# W024X.net
KiCad netlist of a schematic drawn in EAGLE
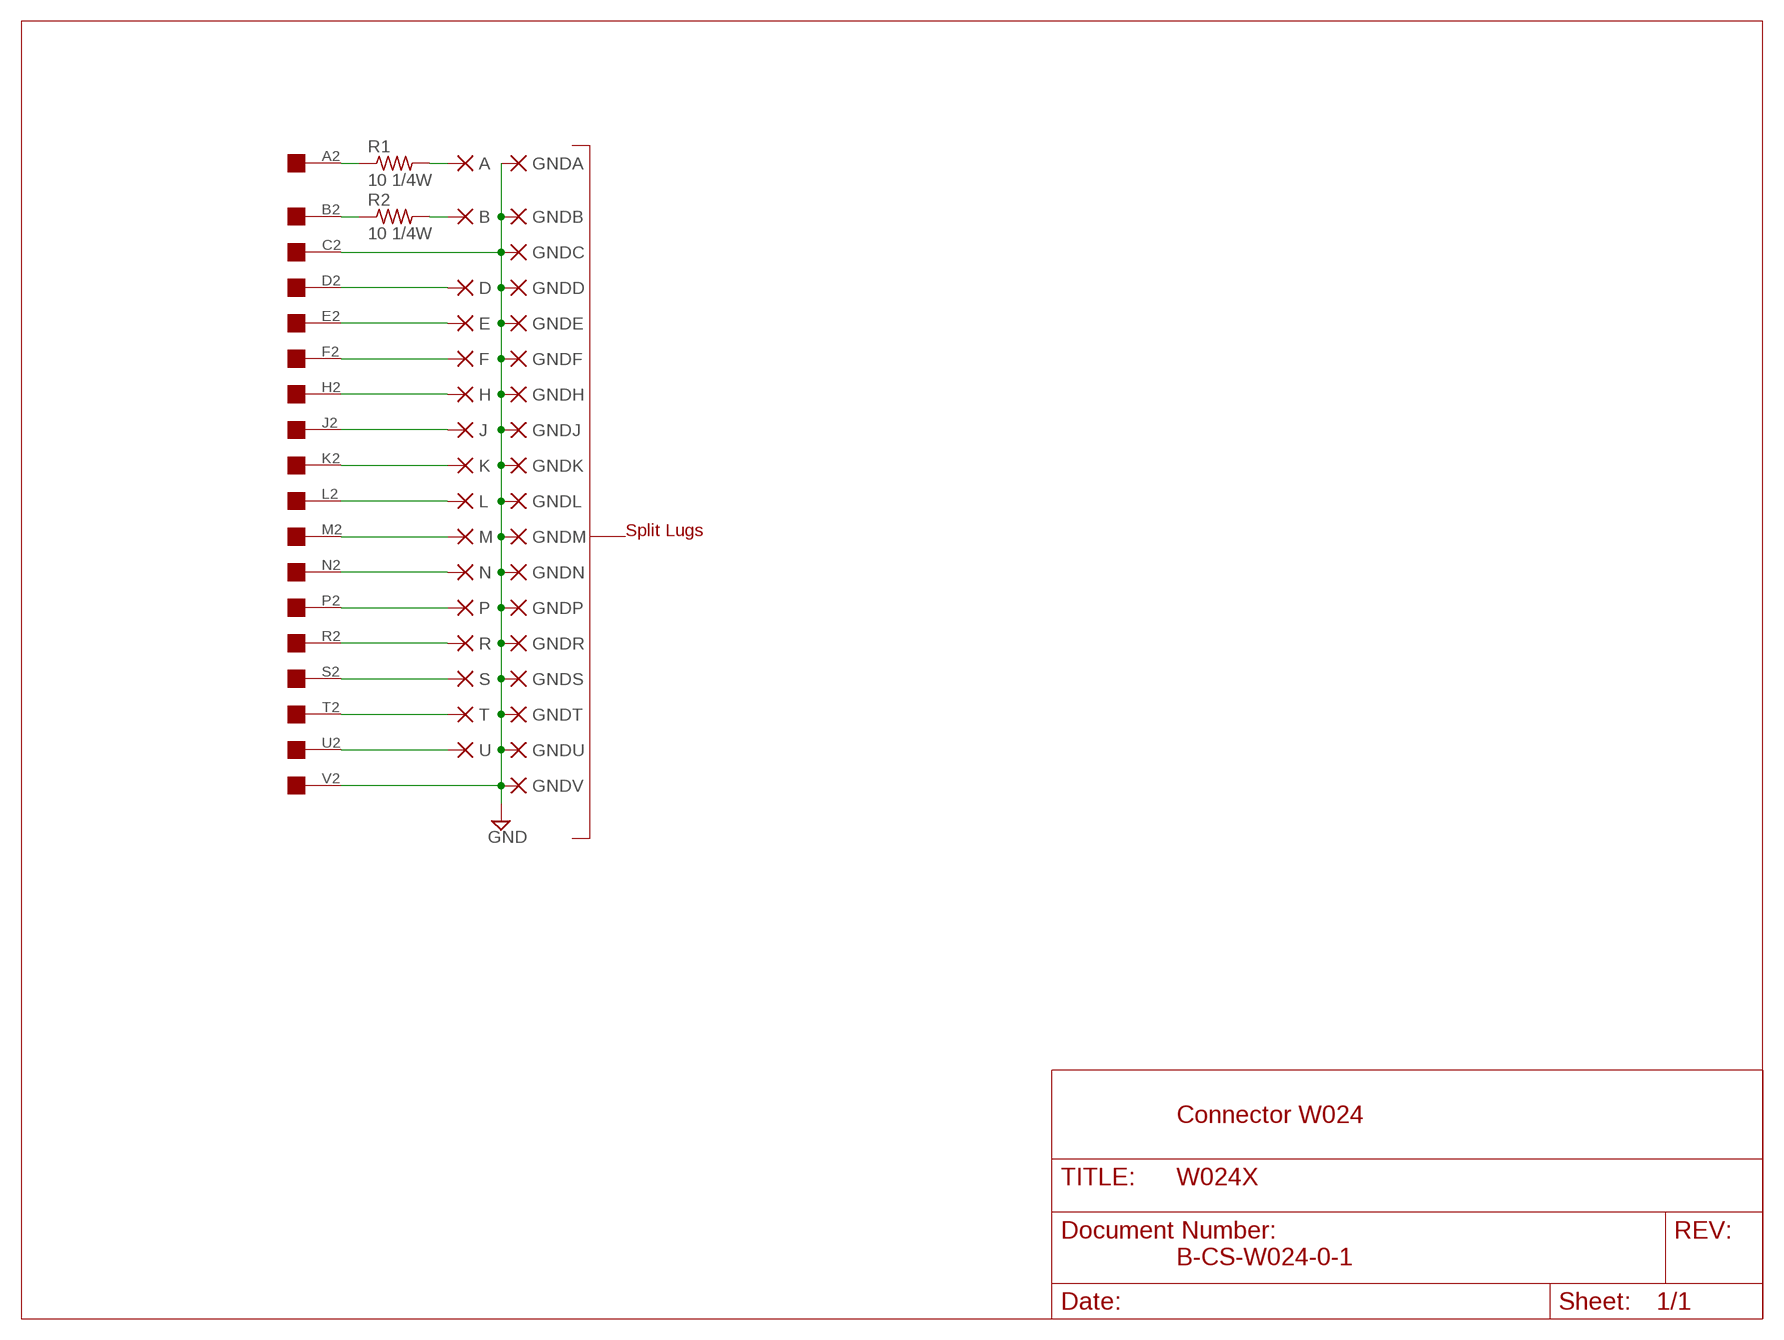
[diagram p0: schematic, sheet 1]

(export (version "E")
  (design (tool "Eeschema 10.0.6"))
  (components
    (comp (ref "A")
      (value "PAD-0465")
      (footprint "eagle-import:0465")
      (libsource (lib "eagle-import") (part "PAD-0465"))
    )
    (comp (ref "B")
      (value "PAD-0465")
      (footprint "eagle-import:0465")
      (libsource (lib "eagle-import") (part "PAD-0465"))
    )
    (comp (ref "D")
      (value "PAD-0465")
      (footprint "eagle-import:0465")
      (libsource (lib "eagle-import") (part "PAD-0465"))
    )
    (comp (ref "E")
      (value "PAD-0465")
      (footprint "eagle-import:0465")
      (libsource (lib "eagle-import") (part "PAD-0465"))
    )
    (comp (ref "F")
      (value "PAD-0465")
      (footprint "eagle-import:0465")
      (libsource (lib "eagle-import") (part "PAD-0465"))
    )
    (comp (ref "GNDA")
      (value "PAD-0465")
      (footprint "eagle-import:0465")
      (libsource (lib "eagle-import") (part "PAD-0465"))
    )
    (comp (ref "GNDB")
      (value "PAD-0465")
      (footprint "eagle-import:0465")
      (libsource (lib "eagle-import") (part "PAD-0465"))
    )
    (comp (ref "GNDC")
      (value "PAD-0465")
      (footprint "eagle-import:0465")
      (libsource (lib "eagle-import") (part "PAD-0465"))
    )
    (comp (ref "GNDD")
      (value "PAD-0465")
      (footprint "eagle-import:0465")
      (libsource (lib "eagle-import") (part "PAD-0465"))
    )
    (comp (ref "GNDE")
      (value "PAD-0465")
      (footprint "eagle-import:0465")
      (libsource (lib "eagle-import") (part "PAD-0465"))
    )
    (comp (ref "GNDF")
      (value "PAD-0465")
      (footprint "eagle-import:0465")
      (libsource (lib "eagle-import") (part "PAD-0465"))
    )
    (comp (ref "GNDH")
      (value "PAD-0465")
      (footprint "eagle-import:0465")
      (libsource (lib "eagle-import") (part "PAD-0465"))
    )
    (comp (ref "GNDJ")
      (value "PAD-0465")
      (footprint "eagle-import:0465")
      (libsource (lib "eagle-import") (part "PAD-0465"))
    )
    (comp (ref "GNDK")
      (value "PAD-0465")
      (footprint "eagle-import:0465")
      (libsource (lib "eagle-import") (part "PAD-0465"))
    )
    (comp (ref "GNDL")
      (value "PAD-0465")
      (footprint "eagle-import:0465")
      (libsource (lib "eagle-import") (part "PAD-0465"))
    )
    (comp (ref "GNDM")
      (value "PAD-0465")
      (footprint "eagle-import:0465")
      (libsource (lib "eagle-import") (part "PAD-0465"))
    )
    (comp (ref "GNDN")
      (value "PAD-0465")
      (footprint "eagle-import:0465")
      (libsource (lib "eagle-import") (part "PAD-0465"))
    )
    (comp (ref "GNDP")
      (value "PAD-0465")
      (footprint "eagle-import:0465")
      (libsource (lib "eagle-import") (part "PAD-0465"))
    )
    (comp (ref "GNDR")
      (value "PAD-0465")
      (footprint "eagle-import:0465")
      (libsource (lib "eagle-import") (part "PAD-0465"))
    )
    (comp (ref "GNDS")
      (value "PAD-0465")
      (footprint "eagle-import:0465")
      (libsource (lib "eagle-import") (part "PAD-0465"))
    )
    (comp (ref "GNDT")
      (value "PAD-0465")
      (footprint "eagle-import:0465")
      (libsource (lib "eagle-import") (part "PAD-0465"))
    )
    (comp (ref "GNDU")
      (value "PAD-0465")
      (footprint "eagle-import:0465")
      (libsource (lib "eagle-import") (part "PAD-0465"))
    )
    (comp (ref "GNDV")
      (value "PAD-0465")
      (footprint "eagle-import:0465")
      (libsource (lib "eagle-import") (part "PAD-0465"))
    )
    (comp (ref "H")
      (value "PAD-0465")
      (footprint "eagle-import:0465")
      (libsource (lib "eagle-import") (part "PAD-0465"))
    )
    (comp (ref "J")
      (value "PAD-0465")
      (footprint "eagle-import:0465")
      (libsource (lib "eagle-import") (part "PAD-0465"))
    )
    (comp (ref "K")
      (value "PAD-0465")
      (footprint "eagle-import:0465")
      (libsource (lib "eagle-import") (part "PAD-0465"))
    )
    (comp (ref "L")
      (value "PAD-0465")
      (footprint "eagle-import:0465")
      (libsource (lib "eagle-import") (part "PAD-0465"))
    )
    (comp (ref "M")
      (value "PAD-0465")
      (footprint "eagle-import:0465")
      (libsource (lib "eagle-import") (part "PAD-0465"))
    )
    (comp (ref "N")
      (value "PAD-0465")
      (footprint "eagle-import:0465")
      (libsource (lib "eagle-import") (part "PAD-0465"))
    )
    (comp (ref "P")
      (value "PAD-0465")
      (footprint "eagle-import:0465")
      (libsource (lib "eagle-import") (part "PAD-0465"))
    )
    (comp (ref "R")
      (value "PAD-0465")
      (footprint "eagle-import:0465")
      (libsource (lib "eagle-import") (part "PAD-0465"))
    )
    (comp (ref "R1")
      (value "10 1/4W")
      (footprint "eagle-import:0207_10")
      (libsource (lib "eagle-import") (part "R-US_0207/10"))
    )
    (comp (ref "R2")
      (value "10 1/4W")
      (footprint "eagle-import:0207_10")
      (libsource (lib "eagle-import") (part "R-US_0207/10"))
    )
    (comp (ref "S")
      (value "PAD-0465")
      (footprint "eagle-import:0465")
      (libsource (lib "eagle-import") (part "PAD-0465"))
    )
    (comp (ref "T")
      (value "PAD-0465")
      (footprint "eagle-import:0465")
      (libsource (lib "eagle-import") (part "PAD-0465"))
    )
    (comp (ref "U")
      (value "PAD-0465")
      (footprint "eagle-import:0465")
      (libsource (lib "eagle-import") (part "PAD-0465"))
    )
    (comp (ref "U$2")
      (value "EDGE-1")
      (footprint "eagle-import:EDGE-CON1")
      (libsource (lib "eagle-import") (part "EDGE-1"))
    )
  )
  (nets
    (net (code "1") (name "GND") (class "Default")
      (node (ref "GNDA") (pin "P$1") (pinfunction "P_P$1") (pintype "passive"))
      (node (ref "GNDB") (pin "P$1") (pinfunction "P_P$1") (pintype "passive"))
      (node (ref "GNDC") (pin "P$1") (pinfunction "P_P$1") (pintype "passive"))
      (node (ref "GNDD") (pin "P$1") (pinfunction "P_P$1") (pintype "passive"))
      (node (ref "GNDE") (pin "P$1") (pinfunction "P_P$1") (pintype "passive"))
      (node (ref "GNDF") (pin "P$1") (pinfunction "P_P$1") (pintype "passive"))
      (node (ref "GNDH") (pin "P$1") (pinfunction "P_P$1") (pintype "passive"))
      (node (ref "GNDJ") (pin "P$1") (pinfunction "P_P$1") (pintype "passive"))
      (node (ref "GNDK") (pin "P$1") (pinfunction "P_P$1") (pintype "passive"))
      (node (ref "GNDL") (pin "P$1") (pinfunction "P_P$1") (pintype "passive"))
      (node (ref "GNDM") (pin "P$1") (pinfunction "P_P$1") (pintype "passive"))
      (node (ref "GNDN") (pin "P$1") (pinfunction "P_P$1") (pintype "passive"))
      (node (ref "GNDP") (pin "P$1") (pinfunction "P_P$1") (pintype "passive"))
      (node (ref "GNDR") (pin "P$1") (pinfunction "P_P$1") (pintype "passive"))
      (node (ref "GNDS") (pin "P$1") (pinfunction "P_P$1") (pintype "passive"))
      (node (ref "GNDT") (pin "P$1") (pinfunction "P_P$1") (pintype "passive"))
      (node (ref "GNDU") (pin "P$1") (pinfunction "P_P$1") (pintype "passive"))
      (node (ref "GNDV") (pin "P$1") (pinfunction "P_P$1") (pintype "passive"))
      (node (ref "U$2") (pin "C2") (pinfunction "1_C2") (pintype "bidirectional"))
      (node (ref "U$2") (pin "V2") (pinfunction "1_V2") (pintype "bidirectional"))
    )
    (net (code "2") (name "Net-(A-P)") (class "Default")
      (node (ref "A") (pin "P$1") (pinfunction "P_P$1") (pintype "passive"))
      (node (ref "R1") (pin "2") (pinfunction "2_2") (pintype "passive"))
    )
    (net (code "3") (name "Net-(B-P)") (class "Default")
      (node (ref "B") (pin "P$1") (pinfunction "P_P$1") (pintype "passive"))
      (node (ref "R2") (pin "2") (pinfunction "2_2") (pintype "passive"))
    )
    (net (code "4") (name "Net-(D-P)") (class "Default")
      (node (ref "D") (pin "P$1") (pinfunction "P_P$1") (pintype "passive"))
      (node (ref "U$2") (pin "D2") (pinfunction "1_D2") (pintype "bidirectional"))
    )
    (net (code "5") (name "Net-(E-P)") (class "Default")
      (node (ref "E") (pin "P$1") (pinfunction "P_P$1") (pintype "passive"))
      (node (ref "U$2") (pin "E2") (pinfunction "1_E2") (pintype "bidirectional"))
    )
    (net (code "6") (name "Net-(F-P)") (class "Default")
      (node (ref "F") (pin "P$1") (pinfunction "P_P$1") (pintype "passive"))
      (node (ref "U$2") (pin "F2") (pinfunction "1_F2") (pintype "bidirectional"))
    )
    (net (code "7") (name "Net-(H-P)") (class "Default")
      (node (ref "H") (pin "P$1") (pinfunction "P_P$1") (pintype "passive"))
      (node (ref "U$2") (pin "H2") (pinfunction "1_H2") (pintype "bidirectional"))
    )
    (net (code "8") (name "Net-(J-P)") (class "Default")
      (node (ref "J") (pin "P$1") (pinfunction "P_P$1") (pintype "passive"))
      (node (ref "U$2") (pin "J2") (pinfunction "1_J2") (pintype "bidirectional"))
    )
    (net (code "9") (name "Net-(K-P)") (class "Default")
      (node (ref "K") (pin "P$1") (pinfunction "P_P$1") (pintype "passive"))
      (node (ref "U$2") (pin "K2") (pinfunction "1_K2") (pintype "bidirectional"))
    )
    (net (code "10") (name "Net-(L-P)") (class "Default")
      (node (ref "L") (pin "P$1") (pinfunction "P_P$1") (pintype "passive"))
      (node (ref "U$2") (pin "L2") (pinfunction "1_L2") (pintype "bidirectional"))
    )
    (net (code "11") (name "Net-(M-P)") (class "Default")
      (node (ref "M") (pin "P$1") (pinfunction "P_P$1") (pintype "passive"))
      (node (ref "U$2") (pin "M2") (pinfunction "1_M2") (pintype "bidirectional"))
    )
    (net (code "12") (name "Net-(N-P)") (class "Default")
      (node (ref "N") (pin "P$1") (pinfunction "P_P$1") (pintype "passive"))
      (node (ref "U$2") (pin "N2") (pinfunction "1_N2") (pintype "bidirectional"))
    )
    (net (code "13") (name "Net-(P-P)") (class "Default")
      (node (ref "P") (pin "P$1") (pinfunction "P_P$1") (pintype "passive"))
      (node (ref "U$2") (pin "P2") (pinfunction "1_P2") (pintype "bidirectional"))
    )
    (net (code "14") (name "Net-(R-P)") (class "Default")
      (node (ref "R") (pin "P$1") (pinfunction "P_P$1") (pintype "passive"))
      (node (ref "U$2") (pin "R2") (pinfunction "1_R2") (pintype "bidirectional"))
    )
    (net (code "15") (name "Net-(S-P)") (class "Default")
      (node (ref "S") (pin "P$1") (pinfunction "P_P$1") (pintype "passive"))
      (node (ref "U$2") (pin "S2") (pinfunction "1_S2") (pintype "bidirectional"))
    )
    (net (code "16") (name "Net-(T-P)") (class "Default")
      (node (ref "T") (pin "P$1") (pinfunction "P_P$1") (pintype "passive"))
      (node (ref "U$2") (pin "T2") (pinfunction "1_T2") (pintype "bidirectional"))
    )
    (net (code "17") (name "Net-(U$2A-1)") (class "Default")
      (node (ref "R1") (pin "1") (pinfunction "1_1") (pintype "passive"))
      (node (ref "U$2") (pin "A2") (pinfunction "1_A2") (pintype "bidirectional"))
    )
    (net (code "18") (name "Net-(U$2B-1)") (class "Default")
      (node (ref "R2") (pin "1") (pinfunction "1_1") (pintype "passive"))
      (node (ref "U$2") (pin "B2") (pinfunction "1_B2") (pintype "bidirectional"))
    )
    (net (code "19") (name "Net-(U$2Q-1)") (class "Default")
      (node (ref "U") (pin "P$1") (pinfunction "P_P$1") (pintype "passive"))
      (node (ref "U$2") (pin "U2") (pinfunction "1_U2") (pintype "bidirectional"))
    )
  )
)
